# ahdr.net
KiCad netlist of a schematic drawn in EAGLE
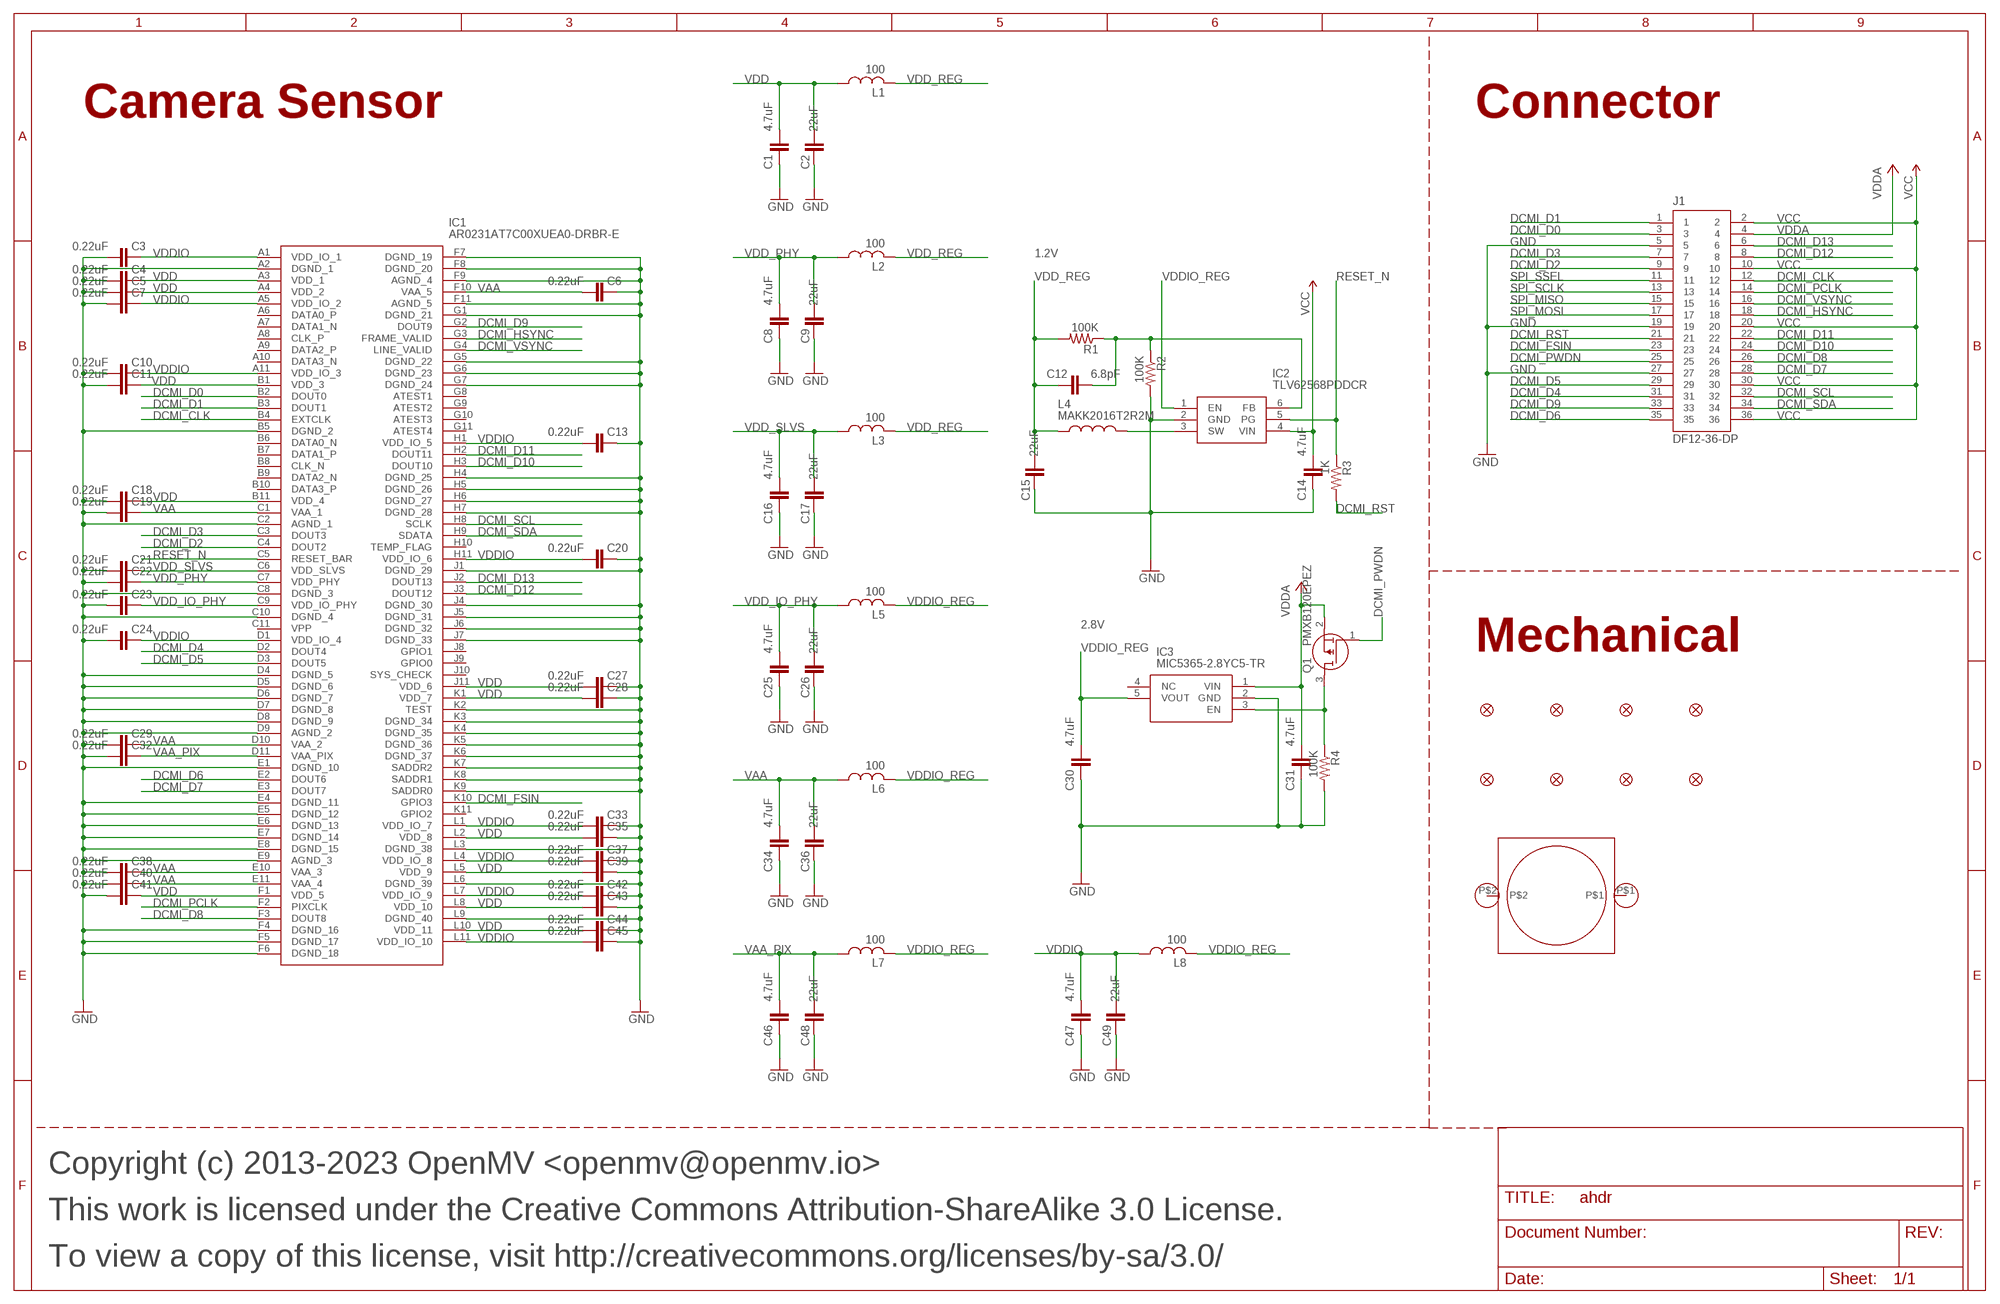
[diagram p0: schematic, sheet 1]

(export (version "E")
  (design (tool "Eeschema 10.0.6"))
  (components
    (comp (ref "C1")
      (value "4.7uF")
      (footprint "eagle-import:0402")
      (fields (field (name "MPN") "JMK105BBJ475MV-F"))
      (libsource (lib "eagle-import") (part "CAP_0402"))
    )
    (comp (ref "C2")
      (value "22uF")
      (footprint "eagle-import:0805")
      (fields (field (name "MPN") "CL21A226MQQNNNE"))
      (libsource (lib "eagle-import") (part "22UF-0805-6.3V-20%"))
    )
    (comp (ref "C3")
      (value "0.22uF")
      (footprint "eagle-import:C0201")
      (fields (field (name "MPN") "GRM033R60J224ME15D"))
      (libsource (lib "eagle-import") (part "C-EUC0201"))
    )
    (comp (ref "C4")
      (value "0.22uF")
      (footprint "eagle-import:C0201")
      (fields (field (name "MPN") "GRM033R60J224ME15D"))
      (libsource (lib "eagle-import") (part "C-EUC0201"))
    )
    (comp (ref "C5")
      (value "0.22uF")
      (footprint "eagle-import:C0201")
      (fields (field (name "MPN") "GRM033R60J224ME15D"))
      (libsource (lib "eagle-import") (part "C-EUC0201"))
    )
    (comp (ref "C6")
      (value "0.22uF")
      (footprint "eagle-import:C0201")
      (fields (field (name "MPN") "GRM033R60J224ME15D"))
      (libsource (lib "eagle-import") (part "C-EUC0201"))
    )
    (comp (ref "C7")
      (value "0.22uF")
      (footprint "eagle-import:C0201")
      (fields (field (name "MPN") "GRM033R60J224ME15D"))
      (libsource (lib "eagle-import") (part "C-EUC0201"))
    )
    (comp (ref "C8")
      (value "4.7uF")
      (footprint "eagle-import:0402")
      (fields (field (name "MPN") "JMK105BBJ475MV-F"))
      (libsource (lib "eagle-import") (part "CAP_0402"))
    )
    (comp (ref "C9")
      (value "22uF")
      (footprint "eagle-import:0805")
      (fields (field (name "MPN") "CL21A226MQQNNNE"))
      (libsource (lib "eagle-import") (part "22UF-0805-6.3V-20%"))
    )
    (comp (ref "C10")
      (value "0.22uF")
      (footprint "eagle-import:C0201")
      (fields (field (name "MPN") "GRM033R60J224ME15D"))
      (libsource (lib "eagle-import") (part "C-EUC0201"))
    )
    (comp (ref "C11")
      (value "0.22uF")
      (footprint "eagle-import:C0201")
      (fields (field (name "MPN") "GRM033R60J224ME15D"))
      (libsource (lib "eagle-import") (part "C-EUC0201"))
    )
    (comp (ref "C12")
      (value "6.8pF")
      (footprint "eagle-import:0402")
      (fields (field (name "MPN") "GRM1555C1H6R8DA01D"))
      (libsource (lib "eagle-import") (part "CAP_0402"))
    )
    (comp (ref "C13")
      (value "0.22uF")
      (footprint "eagle-import:C0201")
      (fields (field (name "MPN") "GRM033R60J224ME15D"))
      (libsource (lib "eagle-import") (part "C-EUC0201"))
    )
    (comp (ref "C14")
      (value "4.7uF")
      (footprint "eagle-import:0402")
      (fields (field (name "MPN") "JMK105BBJ475MV-F"))
      (libsource (lib "eagle-import") (part "CAP_0402"))
    )
    (comp (ref "C15")
      (value "22uF")
      (footprint "eagle-import:0805")
      (fields (field (name "MPN") "CL21A226MQQNNNE"))
      (libsource (lib "eagle-import") (part "22UF-0805-6.3V-20%"))
    )
    (comp (ref "C16")
      (value "4.7uF")
      (footprint "eagle-import:0402")
      (fields (field (name "MPN") "JMK105BBJ475MV-F"))
      (libsource (lib "eagle-import") (part "CAP_0402"))
    )
    (comp (ref "C17")
      (value "22uF")
      (footprint "eagle-import:0805")
      (fields (field (name "MPN") "CL21A226MQQNNNE"))
      (libsource (lib "eagle-import") (part "22UF-0805-6.3V-20%"))
    )
    (comp (ref "C18")
      (value "0.22uF")
      (footprint "eagle-import:C0201")
      (fields (field (name "MPN") "GRM033R60J224ME15D"))
      (libsource (lib "eagle-import") (part "C-EUC0201"))
    )
    (comp (ref "C19")
      (value "0.22uF")
      (footprint "eagle-import:C0201")
      (fields (field (name "MPN") "GRM033R60J224ME15D"))
      (libsource (lib "eagle-import") (part "C-EUC0201"))
    )
    (comp (ref "C20")
      (value "0.22uF")
      (footprint "eagle-import:C0201")
      (fields (field (name "MPN") "GRM033R60J224ME15D"))
      (libsource (lib "eagle-import") (part "C-EUC0201"))
    )
    (comp (ref "C21")
      (value "0.22uF")
      (footprint "eagle-import:C0201")
      (fields (field (name "MPN") "GRM033R60J224ME15D"))
      (libsource (lib "eagle-import") (part "C-EUC0201"))
    )
    (comp (ref "C22")
      (value "0.22uF")
      (footprint "eagle-import:C0201")
      (fields (field (name "MPN") "GRM033R60J224ME15D"))
      (libsource (lib "eagle-import") (part "C-EUC0201"))
    )
    (comp (ref "C23")
      (value "0.22uF")
      (footprint "eagle-import:C0201")
      (fields (field (name "MPN") "GRM033R60J224ME15D"))
      (libsource (lib "eagle-import") (part "C-EUC0201"))
    )
    (comp (ref "C24")
      (value "0.22uF")
      (footprint "eagle-import:C0201")
      (fields (field (name "MPN") "GRM033R60J224ME15D"))
      (libsource (lib "eagle-import") (part "C-EUC0201"))
    )
    (comp (ref "C25")
      (value "4.7uF")
      (footprint "eagle-import:0402")
      (fields (field (name "MPN") "JMK105BBJ475MV-F"))
      (libsource (lib "eagle-import") (part "CAP_0402"))
    )
    (comp (ref "C26")
      (value "22uF")
      (footprint "eagle-import:0805")
      (fields (field (name "MPN") "CL21A226MQQNNNE"))
      (libsource (lib "eagle-import") (part "22UF-0805-6.3V-20%"))
    )
    (comp (ref "C27")
      (value "0.22uF")
      (footprint "eagle-import:C0201")
      (fields (field (name "MPN") "GRM033R60J224ME15D"))
      (libsource (lib "eagle-import") (part "C-EUC0201"))
    )
    (comp (ref "C28")
      (value "0.22uF")
      (footprint "eagle-import:C0201")
      (fields (field (name "MPN") "GRM033R60J224ME15D"))
      (libsource (lib "eagle-import") (part "C-EUC0201"))
    )
    (comp (ref "C29")
      (value "0.22uF")
      (footprint "eagle-import:C0201")
      (fields (field (name "MPN") "GRM033R60J224ME15D"))
      (libsource (lib "eagle-import") (part "C-EUC0201"))
    )
    (comp (ref "C30")
      (value "4.7uF")
      (footprint "eagle-import:0402")
      (fields (field (name "MPN") "JMK105BBJ475MV-F"))
      (libsource (lib "eagle-import") (part "CAP_0402"))
    )
    (comp (ref "C31")
      (value "4.7uF")
      (footprint "eagle-import:0402")
      (fields (field (name "MPN") "JMK105BBJ475MV-F"))
      (libsource (lib "eagle-import") (part "CAP_0402"))
    )
    (comp (ref "C32")
      (value "0.22uF")
      (footprint "eagle-import:C0201")
      (fields (field (name "MPN") "GRM033R60J224ME15D"))
      (libsource (lib "eagle-import") (part "C-EUC0201"))
    )
    (comp (ref "C33")
      (value "0.22uF")
      (footprint "eagle-import:C0201")
      (fields (field (name "MPN") "GRM033R60J224ME15D"))
      (libsource (lib "eagle-import") (part "C-EUC0201"))
    )
    (comp (ref "C34")
      (value "4.7uF")
      (footprint "eagle-import:0402")
      (fields (field (name "MPN") "JMK105BBJ475MV-F"))
      (libsource (lib "eagle-import") (part "CAP_0402"))
    )
    (comp (ref "C35")
      (value "0.22uF")
      (footprint "eagle-import:C0201")
      (fields (field (name "MPN") "GRM033R60J224ME15D"))
      (libsource (lib "eagle-import") (part "C-EUC0201"))
    )
    (comp (ref "C36")
      (value "22uF")
      (footprint "eagle-import:0805")
      (fields (field (name "MPN") "CL21A226MQQNNNE"))
      (libsource (lib "eagle-import") (part "22UF-0805-6.3V-20%"))
    )
    (comp (ref "C37")
      (value "0.22uF")
      (footprint "eagle-import:C0201")
      (fields (field (name "MPN") "GRM033R60J224ME15D"))
      (libsource (lib "eagle-import") (part "C-EUC0201"))
    )
    (comp (ref "C38")
      (value "0.22uF")
      (footprint "eagle-import:C0201")
      (fields (field (name "MPN") "GRM033R60J224ME15D"))
      (libsource (lib "eagle-import") (part "C-EUC0201"))
    )
    (comp (ref "C39")
      (value "0.22uF")
      (footprint "eagle-import:C0201")
      (fields (field (name "MPN") "GRM033R60J224ME15D"))
      (libsource (lib "eagle-import") (part "C-EUC0201"))
    )
    (comp (ref "C40")
      (value "0.22uF")
      (footprint "eagle-import:C0201")
      (fields (field (name "MPN") "GRM033R60J224ME15D"))
      (libsource (lib "eagle-import") (part "C-EUC0201"))
    )
    (comp (ref "C41")
      (value "0.22uF")
      (footprint "eagle-import:C0201")
      (fields (field (name "MPN") "GRM033R60J224ME15D"))
      (libsource (lib "eagle-import") (part "C-EUC0201"))
    )
    (comp (ref "C42")
      (value "0.22uF")
      (footprint "eagle-import:C0201")
      (fields (field (name "MPN") "GRM033R60J224ME15D"))
      (libsource (lib "eagle-import") (part "C-EUC0201"))
    )
    (comp (ref "C43")
      (value "0.22uF")
      (footprint "eagle-import:C0201")
      (fields (field (name "MPN") "GRM033R60J224ME15D"))
      (libsource (lib "eagle-import") (part "C-EUC0201"))
    )
    (comp (ref "C44")
      (value "0.22uF")
      (footprint "eagle-import:C0201")
      (fields (field (name "MPN") "GRM033R60J224ME15D"))
      (libsource (lib "eagle-import") (part "C-EUC0201"))
    )
    (comp (ref "C45")
      (value "0.22uF")
      (footprint "eagle-import:C0201")
      (fields (field (name "MPN") "GRM033R60J224ME15D"))
      (libsource (lib "eagle-import") (part "C-EUC0201"))
    )
    (comp (ref "C46")
      (value "4.7uF")
      (footprint "eagle-import:0402")
      (fields (field (name "MPN") "JMK105BBJ475MV-F"))
      (libsource (lib "eagle-import") (part "CAP_0402"))
    )
    (comp (ref "C47")
      (value "4.7uF")
      (footprint "eagle-import:0402")
      (fields (field (name "MPN") "JMK105BBJ475MV-F"))
      (libsource (lib "eagle-import") (part "CAP_0402"))
    )
    (comp (ref "C48")
      (value "22uF")
      (footprint "eagle-import:0805")
      (fields (field (name "MPN") "CL21A226MQQNNNE"))
      (libsource (lib "eagle-import") (part "22UF-0805-6.3V-20%"))
    )
    (comp (ref "C49")
      (value "22uF")
      (footprint "eagle-import:0805")
      (fields (field (name "MPN") "CL21A226MQQNNNE"))
      (libsource (lib "eagle-import") (part "22UF-0805-6.3V-20%"))
    )
    (comp (ref "FD1")
      (value "FIDUCIAL1X2")
      (footprint "eagle-import:FIDUCIAL-1X2")
      (libsource (lib "eagle-import") (part "FIDUCIAL1X2"))
    )
    (comp (ref "FD2")
      (value "FIDUCIAL1X2")
      (footprint "eagle-import:FIDUCIAL-1X2")
      (libsource (lib "eagle-import") (part "FIDUCIAL1X2"))
    )
    (comp (ref "FD3")
      (value "FIDUCIAL1X2")
      (footprint "eagle-import:FIDUCIAL-1X2")
      (libsource (lib "eagle-import") (part "FIDUCIAL1X2"))
    )
    (comp (ref "FD4")
      (value "FIDUCIAL1X2")
      (footprint "eagle-import:FIDUCIAL-1X2")
      (libsource (lib "eagle-import") (part "FIDUCIAL1X2"))
    )
    (comp (ref "FD5")
      (value "FIDUCIAL1X2")
      (footprint "eagle-import:FIDUCIAL-1X2")
      (libsource (lib "eagle-import") (part "FIDUCIAL1X2"))
    )
    (comp (ref "FD6")
      (value "FIDUCIAL1X2")
      (footprint "eagle-import:FIDUCIAL-1X2")
      (libsource (lib "eagle-import") (part "FIDUCIAL1X2"))
    )
    (comp (ref "FD7")
      (value "FIDUCIAL1X2")
      (footprint "eagle-import:FIDUCIAL-1X2")
      (libsource (lib "eagle-import") (part "FIDUCIAL1X2"))
    )
    (comp (ref "FD8")
      (value "FIDUCIAL1X2")
      (footprint "eagle-import:FIDUCIAL-1X2")
      (libsource (lib "eagle-import") (part "FIDUCIAL1X2"))
    )
    (comp (ref "H1")
      (value "LENSMOUNT20MM")
      (footprint "eagle-import:LENSMOUNT-20MM")
      (libsource (lib "eagle-import") (part "LENSMOUNT20MM"))
    )
    (comp (ref "IC1")
      (value "AR0231AT7C00XUEA0-DRBR-E")
      (footprint "eagle-import:BGA121C80P11X11_1100X1000X155")
      (fields (field (name "MPN") "AR0231AT7C00XUEA0-DPBR"))
      (libsource (lib "eagle-import") (part "AR0231AT7C00XUEA0-DRBR-E"))
    )
    (comp (ref "IC2")
      (value "TLV62568PDDCR")
      (footprint "eagle-import:SOT95P280X110-6N")
      (fields (field (name "MOUSER_PART_NUMBER") "595-TLV62568PDDCR"))
      (libsource (lib "eagle-import") (part "TLV62568PDDCR"))
    )
    (comp (ref "IC3")
      (value "MIC5365-2.8YC5-TR")
      (footprint "eagle-import:SOT65P210X110-5N")
      (fields (field (name "MOUSER_PART_NUMBER") "998-MIC5365-2.8YC5TR"))
      (libsource (lib "eagle-import") (part "MIC5365-2.8YC5-TR"))
    )
    (comp (ref "J1")
      (value "DF12-36-DP")
      (footprint "eagle-import:DF12-36-DP")
      (fields (field (name "MPN") "DF12NB(3.0)-36DP-0.5V(51)"))
      (libsource (lib "eagle-import") (part "DF12-36-DP"))
    )
    (comp (ref "L1")
      (value "100")
      (footprint "eagle-import:0402")
      (fields (field (name "MPN") "MFBM1V1005-101-R"))
      (libsource (lib "eagle-import") (part "INDUCTOR_0402"))
    )
    (comp (ref "L2")
      (value "100")
      (footprint "eagle-import:0402")
      (fields (field (name "MPN") "MFBM1V1005-101-R"))
      (libsource (lib "eagle-import") (part "INDUCTOR_0402"))
    )
    (comp (ref "L3")
      (value "100")
      (footprint "eagle-import:0402")
      (fields (field (name "MPN") "MFBM1V1005-101-R"))
      (libsource (lib "eagle-import") (part "INDUCTOR_0402"))
    )
    (comp (ref "L4")
      (value "MAKK2016T2R2M")
      (footprint "eagle-import:INDC2016X100N")
      (fields (field (name "MF") "Taiyo Yuden"))
      (libsource (lib "eagle-import") (part "MAKK2016T2R2M"))
    )
    (comp (ref "L5")
      (value "100")
      (footprint "eagle-import:0402")
      (fields (field (name "MPN") "MFBM1V1005-101-R"))
      (libsource (lib "eagle-import") (part "INDUCTOR_0402"))
    )
    (comp (ref "L6")
      (value "100")
      (footprint "eagle-import:0402")
      (fields (field (name "MPN") "MFBM1V1005-101-R"))
      (libsource (lib "eagle-import") (part "INDUCTOR_0402"))
    )
    (comp (ref "L7")
      (value "100")
      (footprint "eagle-import:0402")
      (fields (field (name "MPN") "MFBM1V1005-101-R"))
      (libsource (lib "eagle-import") (part "INDUCTOR_0402"))
    )
    (comp (ref "L8")
      (value "100")
      (footprint "eagle-import:0402")
      (fields (field (name "MPN") "MFBM1V1005-101-R"))
      (libsource (lib "eagle-import") (part "INDUCTOR_0402"))
    )
    (comp (ref "Q1")
      (value "PMXB120EPEZ")
      (footprint "eagle-import:PMXB120EPEZ")
      (fields (field (name "MOUSER_PART_NUMBER") "771-PMXB120EPEZ"))
      (libsource (lib "eagle-import") (part "PMXB120EPEZ"))
    )
    (comp (ref "R1")
      (value "100K")
      (footprint "eagle-import:R0402")
      (fields (field (name "MPN") "AC0402FR-07100KL"))
      (libsource (lib "eagle-import") (part "R-US_R0402"))
    )
    (comp (ref "R2")
      (value "100K")
      (footprint "eagle-import:R0402")
      (fields (field (name "MPN") "AC0402FR-07100KL"))
      (libsource (lib "eagle-import") (part "R-US_R0402"))
    )
    (comp (ref "R3")
      (value "1K")
      (footprint "eagle-import:R0402")
      (fields (field (name "MPN") "CRCW04021K00FKEDC"))
      (libsource (lib "eagle-import") (part "R-US_R0402"))
    )
    (comp (ref "R4")
      (value "100K")
      (footprint "eagle-import:R0402")
      (fields (field (name "MPN") "AC0402FR-07100KL"))
      (libsource (lib "eagle-import") (part "R-US_R0402"))
    )
  )
  (nets
    (net (code "1") (name "/DCMI_CLK") (class "Default")
      (node (ref "IC1") (pin "B4") (pinfunction "EXTCLK_B4") (pintype "bidirectional"))
      (node (ref "J1") (pin "12") (pinfunction "12_12") (pintype "bidirectional"))
    )
    (net (code "2") (name "/DCMI_D0") (class "Default")
      (node (ref "IC1") (pin "B2") (pinfunction "DOUT0_B2") (pintype "bidirectional"))
      (node (ref "J1") (pin "3") (pinfunction "3_3") (pintype "bidirectional"))
    )
    (net (code "3") (name "/DCMI_D1") (class "Default")
      (node (ref "IC1") (pin "B3") (pinfunction "DOUT1_B3") (pintype "bidirectional"))
      (node (ref "J1") (pin "1") (pinfunction "1_1") (pintype "bidirectional"))
    )
    (net (code "4") (name "/DCMI_D2") (class "Default")
      (node (ref "IC1") (pin "C4") (pinfunction "DOUT2_C4") (pintype "bidirectional"))
      (node (ref "J1") (pin "9") (pinfunction "9_9") (pintype "bidirectional"))
    )
    (net (code "5") (name "/DCMI_D3") (class "Default")
      (node (ref "IC1") (pin "C3") (pinfunction "DOUT3_C3") (pintype "bidirectional"))
      (node (ref "J1") (pin "7") (pinfunction "7_7") (pintype "bidirectional"))
    )
    (net (code "6") (name "/DCMI_D4") (class "Default")
      (node (ref "IC1") (pin "D2") (pinfunction "DOUT4_D2") (pintype "bidirectional"))
      (node (ref "J1") (pin "31") (pinfunction "31_31") (pintype "bidirectional"))
    )
    (net (code "7") (name "/DCMI_D5") (class "Default")
      (node (ref "IC1") (pin "D3") (pinfunction "DOUT5_D3") (pintype "bidirectional"))
      (node (ref "J1") (pin "29") (pinfunction "29_29") (pintype "bidirectional"))
    )
    (net (code "8") (name "/DCMI_D6") (class "Default")
      (node (ref "IC1") (pin "E2") (pinfunction "DOUT6_E2") (pintype "bidirectional"))
      (node (ref "J1") (pin "35") (pinfunction "35_35") (pintype "bidirectional"))
    )
    (net (code "9") (name "/DCMI_D7") (class "Default")
      (node (ref "IC1") (pin "E3") (pinfunction "DOUT7_E3") (pintype "bidirectional"))
      (node (ref "J1") (pin "28") (pinfunction "28_28") (pintype "bidirectional"))
    )
    (net (code "10") (name "/DCMI_D8") (class "Default")
      (node (ref "IC1") (pin "F3") (pinfunction "DOUT8_F3") (pintype "bidirectional"))
      (node (ref "J1") (pin "26") (pinfunction "26_26") (pintype "bidirectional"))
    )
    (net (code "11") (name "/DCMI_D9") (class "Default")
      (node (ref "IC1") (pin "G2") (pinfunction "DOUT9_G2") (pintype "bidirectional"))
      (node (ref "J1") (pin "33") (pinfunction "33_33") (pintype "bidirectional"))
    )
    (net (code "12") (name "/DCMI_D10") (class "Default")
      (node (ref "IC1") (pin "H3") (pinfunction "DOUT10_H3") (pintype "bidirectional"))
      (node (ref "J1") (pin "24") (pinfunction "24_24") (pintype "bidirectional"))
    )
    (net (code "13") (name "/DCMI_D11") (class "Default")
      (node (ref "IC1") (pin "H2") (pinfunction "DOUT11_H2") (pintype "bidirectional"))
      (node (ref "J1") (pin "22") (pinfunction "22_22") (pintype "bidirectional"))
    )
    (net (code "14") (name "/DCMI_D12") (class "Default")
      (node (ref "IC1") (pin "J3") (pinfunction "DOUT12_J3") (pintype "bidirectional"))
      (node (ref "J1") (pin "8") (pinfunction "8_8") (pintype "bidirectional"))
    )
    (net (code "15") (name "/DCMI_D13") (class "Default")
      (node (ref "IC1") (pin "J2") (pinfunction "DOUT13_J2") (pintype "bidirectional"))
      (node (ref "J1") (pin "6") (pinfunction "6_6") (pintype "bidirectional"))
    )
    (net (code "16") (name "/DCMI_FSIN") (class "Default")
      (node (ref "IC1") (pin "K10") (pinfunction "GPIO3_K10") (pintype "bidirectional"))
      (node (ref "J1") (pin "23") (pinfunction "23_23") (pintype "bidirectional"))
    )
    (net (code "17") (name "/DCMI_HSYNC") (class "Default")
      (node (ref "IC1") (pin "G3") (pinfunction "FRAME_VALID_G3") (pintype "bidirectional"))
      (node (ref "J1") (pin "18") (pinfunction "18_18") (pintype "bidirectional"))
    )
    (net (code "18") (name "/DCMI_PCLK") (class "Default")
      (node (ref "IC1") (pin "F2") (pinfunction "PIXCLK_F2") (pintype "bidirectional"))
      (node (ref "J1") (pin "14") (pinfunction "14_14") (pintype "bidirectional"))
    )
    (net (code "19") (name "/DCMI_PWDN") (class "Default")
      (node (ref "J1") (pin "25") (pinfunction "25_25") (pintype "bidirectional"))
      (node (ref "Q1") (pin "1") (pinfunction "G_1") (pintype "bidirectional"))
    )
    (net (code "20") (name "/DCMI_RST") (class "Default")
      (node (ref "J1") (pin "21") (pinfunction "21_21") (pintype "bidirectional"))
      (node (ref "R3") (pin "2") (pinfunction "2_2") (pintype "passive"))
    )
    (net (code "21") (name "/DCMI_SCL") (class "Default")
      (node (ref "IC1") (pin "H8") (pinfunction "SCLK_H8") (pintype "bidirectional"))
      (node (ref "J1") (pin "32") (pinfunction "32_32") (pintype "bidirectional"))
    )
    (net (code "22") (name "/DCMI_SDA") (class "Default")
      (node (ref "IC1") (pin "H9") (pinfunction "SDATA_H9") (pintype "bidirectional"))
      (node (ref "J1") (pin "34") (pinfunction "34_34") (pintype "bidirectional"))
    )
    (net (code "23") (name "/DCMI_VSYNC") (class "Default")
      (node (ref "IC1") (pin "G4") (pinfunction "LINE_VALID_G4") (pintype "bidirectional"))
      (node (ref "J1") (pin "16") (pinfunction "16_16") (pintype "bidirectional"))
    )
    (net (code "24") (name "/P$1") (class "Default")
      (node (ref "H1") (pin "P$1") (pinfunction "P$1_P$1") (pintype "power_in"))
    )
    (net (code "25") (name "/P$2") (class "Default")
      (node (ref "H1") (pin "P$2") (pinfunction "P$2_P$2") (pintype "power_in"))
    )
    (net (code "26") (name "/RESET_N") (class "Default")
      (node (ref "IC1") (pin "C5") (pinfunction "RESET_BAR_C5") (pintype "bidirectional"))
      (node (ref "IC2") (pin "5") (pinfunction "PG_5") (pintype "bidirectional"))
      (node (ref "R3") (pin "1") (pinfunction "1_1") (pintype "passive"))
    )
    (net (code "27") (name "/SPI_MISO") (class "Default")
      (node (ref "J1") (pin "15") (pinfunction "15_15") (pintype "bidirectional"))
    )
    (net (code "28") (name "/SPI_MOSI") (class "Default")
      (node (ref "J1") (pin "17") (pinfunction "17_17") (pintype "bidirectional"))
    )
    (net (code "29") (name "/SPI_SCLK") (class "Default")
      (node (ref "J1") (pin "13") (pinfunction "13_13") (pintype "bidirectional"))
    )
    (net (code "30") (name "/SPI_SSEL") (class "Default")
      (node (ref "J1") (pin "11") (pinfunction "11_11") (pintype "bidirectional"))
    )
    (net (code "31") (name "/VAA") (class "Default")
      (node (ref "C19") (pin "1") (pinfunction "1_1") (pintype "passive"))
      (node (ref "C29") (pin "1") (pinfunction "1_1") (pintype "passive"))
      (node (ref "C34") (pin "2") (pinfunction "2_2") (pintype "passive"))
      (node (ref "C36") (pin "2") (pinfunction "2_2") (pintype "passive"))
      (node (ref "C38") (pin "1") (pinfunction "1_1") (pintype "passive"))
      (node (ref "C40") (pin "1") (pinfunction "1_1") (pintype "passive"))
      (node (ref "C6") (pin "2") (pinfunction "2_2") (pintype "passive"))
      (node (ref "IC1") (pin "C1") (pinfunction "VAA_1_C1") (pintype "bidirectional"))
      (node (ref "IC1") (pin "D10") (pinfunction "VAA_2_D10") (pintype "bidirectional"))
      (node (ref "IC1") (pin "E10") (pinfunction "VAA_3_E10") (pintype "bidirectional"))
      (node (ref "IC1") (pin "E11") (pinfunction "VAA_4_E11") (pintype "bidirectional"))
      (node (ref "IC1") (pin "F10") (pinfunction "VAA_5_F10") (pintype "bidirectional"))
      (node (ref "L6") (pin "1") (pinfunction "P$1_1") (pintype "passive"))
    )
    (net (code "32") (name "/VAA_PIX") (class "Default")
      (node (ref "C32") (pin "1") (pinfunction "1_1") (pintype "passive"))
      (node (ref "C46") (pin "2") (pinfunction "2_2") (pintype "passive"))
      (node (ref "C48") (pin "2") (pinfunction "2_2") (pintype "passive"))
      (node (ref "IC1") (pin "D11") (pinfunction "VAA_PIX_D11") (pintype "bidirectional"))
      (node (ref "L7") (pin "1") (pinfunction "P$1_1") (pintype "passive"))
    )
    (net (code "33") (name "/VDD") (class "Default")
      (node (ref "C1") (pin "2") (pinfunction "2_2") (pintype "passive"))
      (node (ref "C11") (pin "1") (pinfunction "1_1") (pintype "passive"))
      (node (ref "C18") (pin "1") (pinfunction "1_1") (pintype "passive"))
      (node (ref "C2") (pin "2") (pinfunction "2_2") (pintype "passive"))
      (node (ref "C27") (pin "2") (pinfunction "2_2") (pintype "passive"))
      (node (ref "C28") (pin "2") (pinfunction "2_2") (pintype "passive"))
      (node (ref "C35") (pin "2") (pinfunction "2_2") (pintype "passive"))
      (node (ref "C39") (pin "2") (pinfunction "2_2") (pintype "passive"))
      (node (ref "C4") (pin "1") (pinfunction "1_1") (pintype "passive"))
      (node (ref "C41") (pin "1") (pinfunction "1_1") (pintype "passive"))
      (node (ref "C43") (pin "2") (pinfunction "2_2") (pintype "passive"))
      (node (ref "C44") (pin "2") (pinfunction "2_2") (pintype "passive"))
      (node (ref "C5") (pin "1") (pinfunction "1_1") (pintype "passive"))
      (node (ref "IC1") (pin "A3") (pinfunction "VDD_1_A3") (pintype "bidirectional"))
      (node (ref "IC1") (pin "A4") (pinfunction "VDD_2_A4") (pintype "bidirectional"))
      (node (ref "IC1") (pin "B1") (pinfunction "VDD_3_B1") (pintype "bidirectional"))
      (node (ref "IC1") (pin "B11") (pinfunction "VDD_4_B11") (pintype "bidirectional"))
      (node (ref "IC1") (pin "F1") (pinfunction "VDD_5_F1") (pintype "bidirectional"))
      (node (ref "IC1") (pin "J11") (pinfunction "VDD_6_J11") (pintype "bidirectional"))
      (node (ref "IC1") (pin "K1") (pinfunction "VDD_7_K1") (pintype "bidirectional"))
      (node (ref "IC1") (pin "L10") (pinfunction "VDD_11_L10") (pintype "bidirectional"))
      (node (ref "IC1") (pin "L2") (pinfunction "VDD_8_L2") (pintype "bidirectional"))
      (node (ref "IC1") (pin "L5") (pinfunction "VDD_9_L5") (pintype "bidirectional"))
      (node (ref "IC1") (pin "L8") (pinfunction "VDD_10_L8") (pintype "bidirectional"))
      (node (ref "L1") (pin "1") (pinfunction "P$1_1") (pintype "passive"))
    )
    (net (code "34") (name "/VDDIO") (class "Default")
      (node (ref "C10") (pin "1") (pinfunction "1_1") (pintype "passive"))
      (node (ref "C13") (pin "2") (pinfunction "2_2") (pintype "passive"))
      (node (ref "C20") (pin "2") (pinfunction "2_2") (pintype "passive"))
      (node (ref "C24") (pin "1") (pinfunction "1_1") (pintype "passive"))
      (node (ref "C3") (pin "1") (pinfunction "1_1") (pintype "passive"))
      (node (ref "C33") (pin "2") (pinfunction "2_2") (pintype "passive"))
      (node (ref "C37") (pin "2") (pinfunction "2_2") (pintype "passive"))
      (node (ref "C42") (pin "2") (pinfunction "2_2") (pintype "passive"))
      (node (ref "C45") (pin "2") (pinfunction "2_2") (pintype "passive"))
      (node (ref "C47") (pin "2") (pinfunction "2_2") (pintype "passive"))
      (node (ref "C49") (pin "2") (pinfunction "2_2") (pintype "passive"))
      (node (ref "C7") (pin "1") (pinfunction "1_1") (pintype "passive"))
      (node (ref "IC1") (pin "A1") (pinfunction "VDD_IO_1_A1") (pintype "bidirectional"))
      (node (ref "IC1") (pin "A11") (pinfunction "VDD_IO_3_A11") (pintype "bidirectional"))
      (node (ref "IC1") (pin "A5") (pinfunction "VDD_IO_2_A5") (pintype "bidirectional"))
      (node (ref "IC1") (pin "D1") (pinfunction "VDD_IO_4_D1") (pintype "bidirectional"))
      (node (ref "IC1") (pin "H1") (pinfunction "VDD_IO_5_H1") (pintype "bidirectional"))
      (node (ref "IC1") (pin "H11") (pinfunction "VDD_IO_6_H11") (pintype "bidirectional"))
      (node (ref "IC1") (pin "L1") (pinfunction "VDD_IO_7_L1") (pintype "bidirectional"))
      (node (ref "IC1") (pin "L11") (pinfunction "VDD_IO_10_L11") (pintype "bidirectional"))
      (node (ref "IC1") (pin "L4") (pinfunction "VDD_IO_8_L4") (pintype "bidirectional"))
      (node (ref "IC1") (pin "L7") (pinfunction "VDD_IO_9_L7") (pintype "bidirectional"))
      (node (ref "L8") (pin "1") (pinfunction "P$1_1") (pintype "passive"))
    )
    (net (code "35") (name "/VDDIO_REG") (class "Default")
      (node (ref "C30") (pin "2") (pinfunction "2_2") (pintype "passive"))
      (node (ref "IC2") (pin "1") (pinfunction "EN_1") (pintype "bidirectional"))
      (node (ref "IC3") (pin "5") (pinfunction "VOUT_5") (pintype "bidirectional"))
      (node (ref "L5") (pin "2") (pinfunction "P$2_2") (pintype "passive"))
      (node (ref "L6") (pin "2") (pinfunction "P$2_2") (pintype "passive"))
      (node (ref "L7") (pin "2") (pinfunction "P$2_2") (pintype "passive"))
      (node (ref "L8") (pin "2") (pinfunction "P$2_2") (pintype "passive"))
    )
    (net (code "36") (name "/VDD_IO_PHY") (class "Default")
      (node (ref "C23") (pin "1") (pinfunction "1_1") (pintype "passive"))
      (node (ref "C25") (pin "2") (pinfunction "2_2") (pintype "passive"))
      (node (ref "C26") (pin "2") (pinfunction "2_2") (pintype "passive"))
      (node (ref "IC1") (pin "C9") (pinfunction "VDD_IO_PHY_C9") (pintype "bidirectional"))
      (node (ref "L5") (pin "1") (pinfunction "P$1_1") (pintype "passive"))
    )
    (net (code "37") (name "/VDD_PHY") (class "Default")
      (node (ref "C22") (pin "1") (pinfunction "1_1") (pintype "passive"))
      (node (ref "C8") (pin "2") (pinfunction "2_2") (pintype "passive"))
      (node (ref "C9") (pin "2") (pinfunction "2_2") (pintype "passive"))
      (node (ref "IC1") (pin "C7") (pinfunction "VDD_PHY_C7") (pintype "bidirectional"))
      (node (ref "L2") (pin "1") (pinfunction "P$1_1") (pintype "passive"))
    )
    (net (code "38") (name "/VDD_REG") (class "Default")
      (node (ref "C12") (pin "1") (pinfunction "1_1") (pintype "passive"))
      (node (ref "C15") (pin "2") (pinfunction "2_2") (pintype "passive"))
      (node (ref "L1") (pin "2") (pinfunction "P$2_2") (pintype "passive"))
      (node (ref "L2") (pin "2") (pinfunction "P$2_2") (pintype "passive"))
      (node (ref "L3") (pin "2") (pinfunction "P$2_2") (pintype "passive"))
      (node (ref "L4") (pin "1") (pinfunction "1_1") (pintype "passive"))
      (node (ref "R1") (pin "2") (pinfunction "2_2") (pintype "passive"))
    )
    (net (code "39") (name "/VDD_SLVS") (class "Default")
      (node (ref "C16") (pin "2") (pinfunction "2_2") (pintype "passive"))
      (node (ref "C17") (pin "2") (pinfunction "2_2") (pintype "passive"))
      (node (ref "C21") (pin "1") (pinfunction "1_1") (pintype "passive"))
      (node (ref "IC1") (pin "C6") (pinfunction "VDD_SLVS_C6") (pintype "bidirectional"))
      (node (ref "L3") (pin "1") (pinfunction "P$1_1") (pintype "passive"))
    )
    (net (code "40") (name "GND") (class "Default")
      (node (ref "C1") (pin "1") (pinfunction "1_1") (pintype "passive"))
      (node (ref "C10") (pin "2") (pinfunction "2_2") (pintype "passive"))
      (node (ref "C11") (pin "2") (pinfunction "2_2") (pintype "passive"))
      (node (ref "C13") (pin "1") (pinfunction "1_1") (pintype "passive"))
      (node (ref "C14") (pin "1") (pinfunction "1_1") (pintype "passive"))
      (node (ref "C15") (pin "1") (pinfunction "1_1") (pintype "passive"))
      (node (ref "C16") (pin "1") (pinfunction "1_1") (pintype "passive"))
      (node (ref "C17") (pin "1") (pinfunction "1_1") (pintype "passive"))
      (node (ref "C18") (pin "2") (pinfunction "2_2") (pintype "passive"))
      (node (ref "C19") (pin "2") (pinfunction "2_2") (pintype "passive"))
      (node (ref "C2") (pin "1") (pinfunction "1_1") (pintype "passive"))
      (node (ref "C20") (pin "1") (pinfunction "1_1") (pintype "passive"))
      (node (ref "C21") (pin "2") (pinfunction "2_2") (pintype "passive"))
      (node (ref "C22") (pin "2") (pinfunction "2_2") (pintype "passive"))
      (node (ref "C23") (pin "2") (pinfunction "2_2") (pintype "passive"))
      (node (ref "C24") (pin "2") (pinfunction "2_2") (pintype "passive"))
      (node (ref "C25") (pin "1") (pinfunction "1_1") (pintype "passive"))
      (node (ref "C26") (pin "1") (pinfunction "1_1") (pintype "passive"))
      (node (ref "C27") (pin "1") (pinfunction "1_1") (pintype "passive"))
      (node (ref "C28") (pin "1") (pinfunction "1_1") (pintype "passive"))
      (node (ref "C29") (pin "2") (pinfunction "2_2") (pintype "passive"))
      (node (ref "C3") (pin "2") (pinfunction "2_2") (pintype "passive"))
      (node (ref "C30") (pin "1") (pinfunction "1_1") (pintype "passive"))
      (node (ref "C31") (pin "1") (pinfunction "1_1") (pintype "passive"))
      (node (ref "C32") (pin "2") (pinfunction "2_2") (pintype "passive"))
      (node (ref "C33") (pin "1") (pinfunction "1_1") (pintype "passive"))
      (node (ref "C34") (pin "1") (pinfunction "1_1") (pintype "passive"))
      (node (ref "C35") (pin "1") (pinfunction "1_1") (pintype "passive"))
      (node (ref "C36") (pin "1") (pinfunction "1_1") (pintype "passive"))
      (node (ref "C37") (pin "1") (pinfunction "1_1") (pintype "passive"))
      (node (ref "C38") (pin "2") (pinfunction "2_2") (pintype "passive"))
      (node (ref "C39") (pin "1") (pinfunction "1_1") (pintype "passive"))
      (node (ref "C4") (pin "2") (pinfunction "2_2") (pintype "passive"))
      (node (ref "C40") (pin "2") (pinfunction "2_2") (pintype "passive"))
      (node (ref "C41") (pin "2") (pinfunction "2_2") (pintype "passive"))
      (node (ref "C42") (pin "1") (pinfunction "1_1") (pintype "passive"))
      (node (ref "C43") (pin "1") (pinfunction "1_1") (pintype "passive"))
      (node (ref "C44") (pin "1") (pinfunction "1_1") (pintype "passive"))
      (node (ref "C45") (pin "1") (pinfunction "1_1") (pintype "passive"))
      (node (ref "C46") (pin "1") (pinfunction "1_1") (pintype "passive"))
      (node (ref "C47") (pin "1") (pinfunction "1_1") (pintype "passive"))
      (node (ref "C48") (pin "1") (pinfunction "1_1") (pintype "passive"))
      (node (ref "C49") (pin "1") (pinfunction "1_1") (pintype "passive"))
      (node (ref "C5") (pin "2") (pinfunction "2_2") (pintype "passive"))
      (node (ref "C6") (pin "1") (pinfunction "1_1") (pintype "passive"))
      (node (ref "C7") (pin "2") (pinfunction "2_2") (pintype "passive"))
      (node (ref "C8") (pin "1") (pinfunction "1_1") (pintype "passive"))
      (node (ref "C9") (pin "1") (pinfunction "1_1") (pintype "passive"))
      (node (ref "IC1") (pin "A2") (pinfunction "DGND_1_A2") (pintype "bidirectional"))
      (node (ref "IC1") (pin "B5") (pinfunction "DGND_2_B5") (pintype "bidirectional"))
      (node (ref "IC1") (pin "C10") (pinfunction "DGND_4_C10") (pintype "bidirectional"))
      (node (ref "IC1") (pin "C2") (pinfunction "AGND_1_C2") (pintype "bidirectional"))
      (node (ref "IC1") (pin "C8") (pinfunction "DGND_3_C8") (pintype "bidirectional"))
      (node (ref "IC1") (pin "D4") (pinfunction "DGND_5_D4") (pintype "bidirectional"))
      (node (ref "IC1") (pin "D5") (pinfunction "DGND_6_D5") (pintype "bidirectional"))
      (node (ref "IC1") (pin "D6") (pinfunction "DGND_7_D6") (pintype "bidirectional"))
      (node (ref "IC1") (pin "D7") (pinfunction "DGND_8_D7") (pintype "bidirectional"))
      (node (ref "IC1") (pin "D8") (pinfunction "DGND_9_D8") (pintype "bidirectional"))
      (node (ref "IC1") (pin "D9") (pinfunction "AGND_2_D9") (pintype "bidirectional"))
      (node (ref "IC1") (pin "E1") (pinfunction "DGND_10_E1") (pintype "bidirectional"))
      (node (ref "IC1") (pin "E4") (pinfunction "DGND_11_E4") (pintype "bidirectional"))
      (node (ref "IC1") (pin "E5") (pinfunction "DGND_12_E5") (pintype "bidirectional"))
      (node (ref "IC1") (pin "E6") (pinfunction "DGND_13_E6") (pintype "bidirectional"))
      (node (ref "IC1") (pin "E7") (pinfunction "DGND_14_E7") (pintype "bidirectional"))
      (node (ref "IC1") (pin "E8") (pinfunction "DGND_15_E8") (pintype "bidirectional"))
      (node (ref "IC1") (pin "E9") (pinfunction "AGND_3_E9") (pintype "bidirectional"))
      (node (ref "IC1") (pin "F11") (pinfunction "AGND_5_F11") (pintype "bidirectional"))
      (node (ref "IC1") (pin "F4") (pinfunction "DGND_16_F4") (pintype "bidirectional"))
      (node (ref "IC1") (pin "F5") (pinfunction "DGND_17_F5") (pintype "bidirectional"))
      (node (ref "IC1") (pin "F6") (pinfunction "DGND_18_F6") (pintype "bidirectional"))
      (node (ref "IC1") (pin "F7") (pinfunction "DGND_19_F7") (pintype "bidirectional"))
      (node (ref "IC1") (pin "F8") (pinfunction "DGND_20_F8") (pintype "bidirectional"))
      (node (ref "IC1") (pin "F9") (pinfunction "AGND_4_F9") (pintype "bidirectional"))
      (node (ref "IC1") (pin "G1") (pinfunction "DGND_21_G1") (pintype "bidirectional"))
      (node (ref "IC1") (pin "G5") (pinfunction "DGND_22_G5") (pintype "bidirectional"))
      (node (ref "IC1") (pin "G6") (pinfunction "DGND_23_G6") (pintype "bidirectional"))
      (node (ref "IC1") (pin "G7") (pinfunction "DGND_24_G7") (pintype "bidirectional"))
      (node (ref "IC1") (pin "H4") (pinfunction "DGND_25_H4") (pintype "bidirectional"))
      (node (ref "IC1") (pin "H5") (pinfunction "DGND_26_H5") (pintype "bidirectional"))
      (node (ref "IC1") (pin "H6") (pinfunction "DGND_27_H6") (pintype "bidirectional"))
      (node (ref "IC1") (pin "H7") (pinfunction "DGND_28_H7") (pintype "bidirectional"))
      (node (ref "IC1") (pin "J1") (pinfunction "DGND_29_J1") (pintype "bidirectional"))
      (node (ref "IC1") (pin "J4") (pinfunction "DGND_30_J4") (pintype "bidirectional"))
      (node (ref "IC1") (pin "J5") (pinfunction "DGND_31_J5") (pintype "bidirectional"))
      (node (ref "IC1") (pin "J6") (pinfunction "DGND_32_J6") (pintype "bidirectional"))
      (node (ref "IC1") (pin "J7") (pinfunction "DGND_33_J7") (pintype "bidirectional"))
      (node (ref "IC1") (pin "K2") (pinfunction "TEST_K2") (pintype "bidirectional"))
      (node (ref "IC1") (pin "K3") (pinfunction "DGND_34_K3") (pintype "bidirectional"))
      (node (ref "IC1") (pin "K4") (pinfunction "DGND_35_K4") (pintype "bidirectional"))
      (node (ref "IC1") (pin "K5") (pinfunction "DGND_36_K5") (pintype "bidirectional"))
      (node (ref "IC1") (pin "K6") (pinfunction "DGND_37_K6") (pintype "bidirectional"))
      (node (ref "IC1") (pin "K7") (pinfunction "SADDR2_K7") (pintype "bidirectional"))
      (node (ref "IC1") (pin "K8") (pinfunction "SADDR1_K8") (pintype "bidirectional"))
      (node (ref "IC1") (pin "K9") (pinfunction "SADDR0_K9") (pintype "bidirectional"))
      (node (ref "IC1") (pin "L3") (pinfunction "DGND_38_L3") (pintype "bidirectional"))
      (node (ref "IC1") (pin "L6") (pinfunction "DGND_39_L6") (pintype "bidirectional"))
      (node (ref "IC1") (pin "L9") (pinfunction "DGND_40_L9") (pintype "bidirectional"))
      (node (ref "IC2") (pin "2") (pinfunction "GND_2") (pintype "bidirectional"))
      (node (ref "IC3") (pin "2") (pinfunction "GND_2") (pintype "bidirectional"))
      (node (ref "J1") (pin "19") (pinfunction "19_19") (pintype "bidirectional"))
      (node (ref "J1") (pin "27") (pinfunction "27_27") (pintype "bidirectional"))
      (node (ref "J1") (pin "5") (pinfunction "5_5") (pintype "bidirectional"))
      (node (ref "R2") (pin "2") (pinfunction "2_2") (pintype "passive"))
      (node (ref "R4") (pin "2") (pinfunction "2_2") (pintype "passive"))
    )
    (net (code "41") (name "Net-(IC2-FB)") (class "Default")
      (node (ref "C12") (pin "2") (pinfunction "2_2") (pintype "passive"))
      (node (ref "IC2") (pin "6") (pinfunction "FB_6") (pintype "bidirectional"))
      (node (ref "R1") (pin "1") (pinfunction "1_1") (pintype "passive"))
      (node (ref "R2") (pin "1") (pinfunction "1_1") (pintype "passive"))
    )
    (net (code "42") (name "Net-(IC2-SW)") (class "Default")
      (node (ref "IC2") (pin "3") (pinfunction "SW_3") (pintype "bidirectional"))
      (node (ref "L4") (pin "2") (pinfunction "2_2") (pintype "passive"))
    )
    (net (code "43") (name "Net-(IC3-EN)") (class "Default")
      (node (ref "IC3") (pin "3") (pinfunction "EN_3") (pintype "bidirectional"))
      (node (ref "Q1") (pin "3") (pinfunction "D_3") (pintype "bidirectional"))
      (node (ref "R4") (pin "1") (pinfunction "1_1") (pintype "passive"))
    )
    (net (code "44") (name "VCC") (class "Default")
      (node (ref "C14") (pin "2") (pinfunction "2_2") (pintype "passive"))
      (node (ref "IC2") (pin "4") (pinfunction "VIN_4") (pintype "bidirectional"))
      (node (ref "J1") (pin "10") (pinfunction "10_10") (pintype "bidirectional"))
      (node (ref "J1") (pin "2") (pinfunction "2_2") (pintype "bidirectional"))
      (node (ref "J1") (pin "20") (pinfunction "20_20") (pintype "bidirectional"))
      (node (ref "J1") (pin "30") (pinfunction "30_30") (pintype "bidirectional"))
      (node (ref "J1") (pin "36") (pinfunction "36_36") (pintype "bidirectional"))
    )
    (net (code "45") (name "VDDA") (class "Default")
      (node (ref "C31") (pin "2") (pinfunction "2_2") (pintype "passive"))
      (node (ref "IC3") (pin "1") (pinfunction "VIN_1") (pintype "bidirectional"))
      (node (ref "J1") (pin "4") (pinfunction "4_4") (pintype "bidirectional"))
      (node (ref "Q1") (pin "2") (pinfunction "S_2") (pintype "bidirectional"))
    )
    (net (code "46") (name "unconnected-(IC1-ATEST1-PadG8)") (class "Default")
      (node (ref "IC1") (pin "G8") (pinfunction "ATEST1_G8") (pintype "bidirectional"))
    )
    (net (code "47") (name "unconnected-(IC1-ATEST2-PadG9)") (class "Default")
      (node (ref "IC1") (pin "G9") (pinfunction "ATEST2_G9") (pintype "bidirectional"))
    )
    (net (code "48") (name "unconnected-(IC1-ATEST3-PadG10)") (class "Default")
      (node (ref "IC1") (pin "G10") (pinfunction "ATEST3_G10") (pintype "bidirectional"))
    )
    (net (code "49") (name "unconnected-(IC1-ATEST4-PadG11)") (class "Default")
      (node (ref "IC1") (pin "G11") (pinfunction "ATEST4_G11") (pintype "bidirectional"))
    )
    (net (code "50") (name "unconnected-(IC1-CLK_N-PadB8)") (class "Default")
      (node (ref "IC1") (pin "B8") (pinfunction "CLK_N_B8") (pintype "bidirectional"))
    )
    (net (code "51") (name "unconnected-(IC1-CLK_P-PadA8)") (class "Default")
      (node (ref "IC1") (pin "A8") (pinfunction "CLK_P_A8") (pintype "bidirectional"))
    )
    (net (code "52") (name "unconnected-(IC1-DATA0_N-PadB6)") (class "Default")
      (node (ref "IC1") (pin "B6") (pinfunction "DATA0_N_B6") (pintype "bidirectional"))
    )
    (net (code "53") (name "unconnected-(IC1-DATA0_P-PadA6)") (class "Default")
      (node (ref "IC1") (pin "A6") (pinfunction "DATA0_P_A6") (pintype "bidirectional"))
    )
    (net (code "54") (name "unconnected-(IC1-DATA1_N-PadA7)") (class "Default")
      (node (ref "IC1") (pin "A7") (pinfunction "DATA1_N_A7") (pintype "bidirectional"))
    )
    (net (code "55") (name "unconnected-(IC1-DATA1_P-PadB7)") (class "Default")
      (node (ref "IC1") (pin "B7") (pinfunction "DATA1_P_B7") (pintype "bidirectional"))
    )
    (net (code "56") (name "unconnected-(IC1-DATA2_N-PadB9)") (class "Default")
      (node (ref "IC1") (pin "B9") (pinfunction "DATA2_N_B9") (pintype "bidirectional"))
    )
    (net (code "57") (name "unconnected-(IC1-DATA2_P-PadA9)") (class "Default")
      (node (ref "IC1") (pin "A9") (pinfunction "DATA2_P_A9") (pintype "bidirectional"))
    )
    (net (code "58") (name "unconnected-(IC1-DATA3_N-PadA10)") (class "Default")
      (node (ref "IC1") (pin "A10") (pinfunction "DATA3_N_A10") (pintype "bidirectional"))
    )
    (net (code "59") (name "unconnected-(IC1-DATA3_P-PadB10)") (class "Default")
      (node (ref "IC1") (pin "B10") (pinfunction "DATA3_P_B10") (pintype "bidirectional"))
    )
    (net (code "60") (name "unconnected-(IC1-GPIO0-PadJ9)") (class "Default")
      (node (ref "IC1") (pin "J9") (pinfunction "GPIO0_J9") (pintype "bidirectional"))
    )
    (net (code "61") (name "unconnected-(IC1-GPIO1-PadJ8)") (class "Default")
      (node (ref "IC1") (pin "J8") (pinfunction "GPIO1_J8") (pintype "bidirectional"))
    )
    (net (code "62") (name "unconnected-(IC1-GPIO2-PadK11)") (class "Default")
      (node (ref "IC1") (pin "K11") (pinfunction "GPIO2_K11") (pintype "bidirectional"))
    )
    (net (code "63") (name "unconnected-(IC1-SYS_CHECK-PadJ10)") (class "Default")
      (node (ref "IC1") (pin "J10") (pinfunction "SYS_CHECK_J10") (pintype "bidirectional"))
    )
    (net (code "64") (name "unconnected-(IC1-TEMP_FLAG-PadH10)") (class "Default")
      (node (ref "IC1") (pin "H10") (pinfunction "TEMP_FLAG_H10") (pintype "bidirectional"))
    )
    (net (code "65") (name "unconnected-(IC1-VPP-PadC11)") (class "Default")
      (node (ref "IC1") (pin "C11") (pinfunction "VPP_C11") (pintype "bidirectional"))
    )
    (net (code "66") (name "unconnected-(IC3-NC-Pad4)") (class "Default")
      (node (ref "IC3") (pin "4") (pinfunction "NC_4") (pintype "no_connect"))
    )
  )
)
